# Rocket_Controller_ver2_00.net
KiCad netlist of a schematic drawn in EAGLE
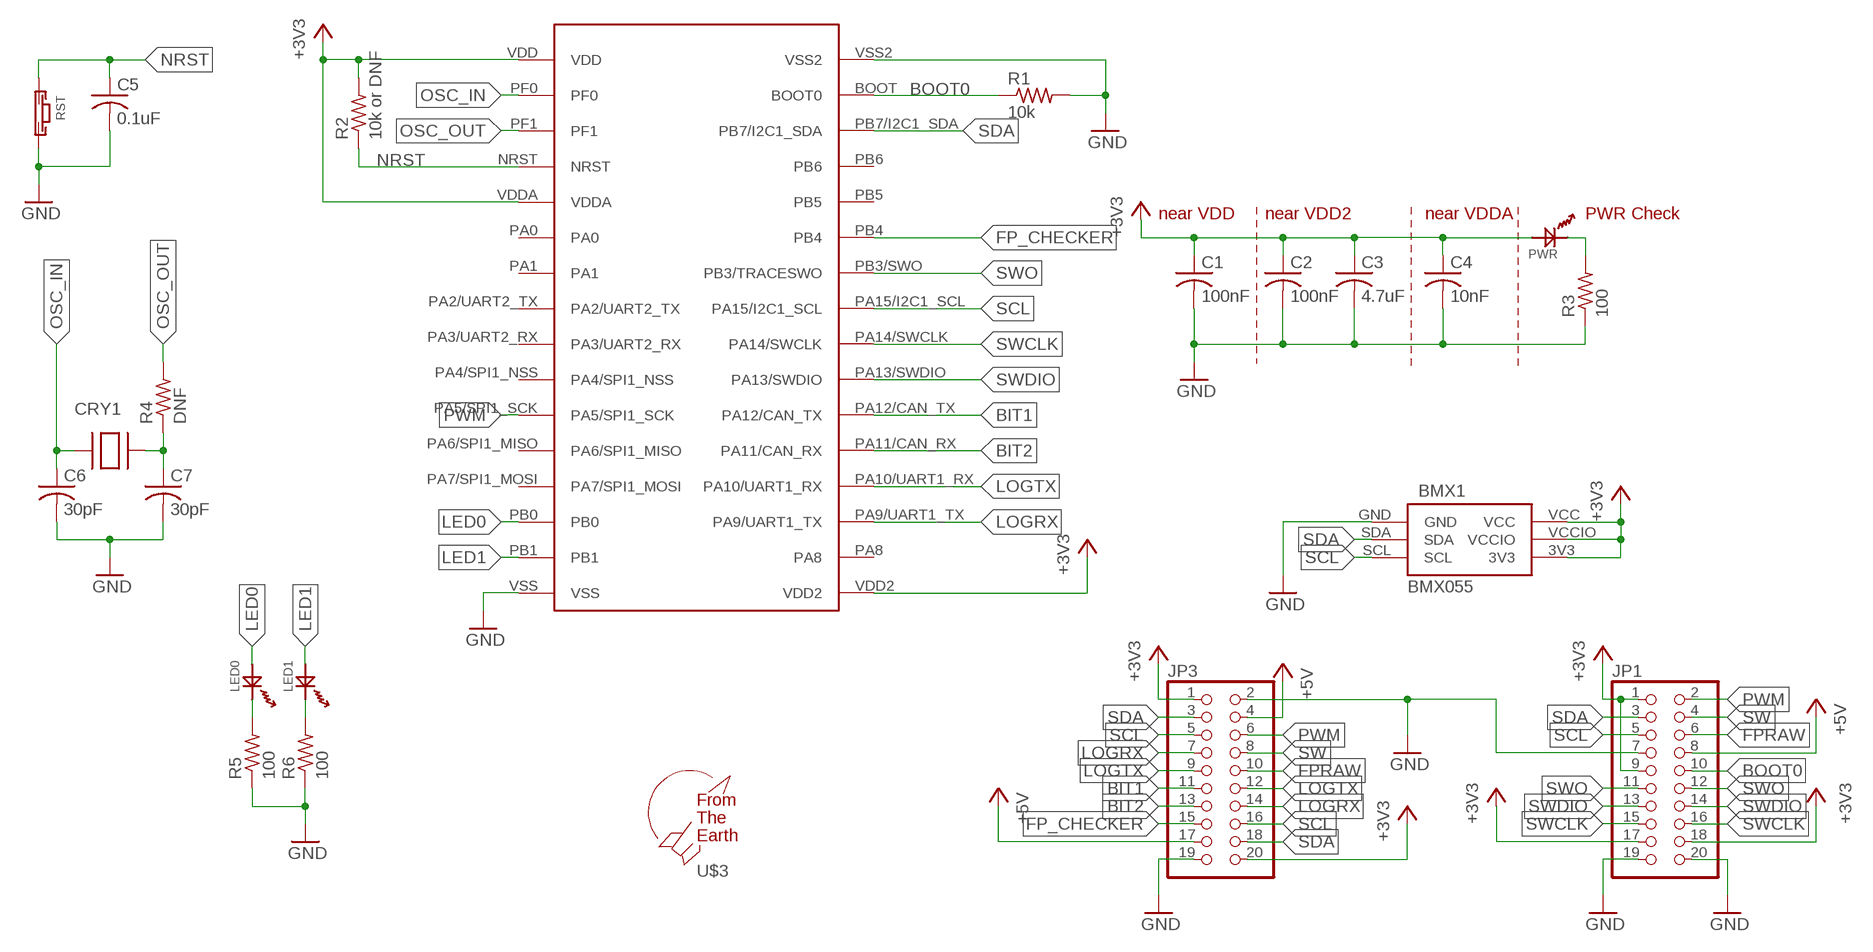
[diagram p0: schematic, sheet 1]

(export (version "E")
  (design (tool "Eeschema 10.0.6"))
  (components
    (comp (ref "BMX1")
      (value "BMX055")
      (footprint "eagle-import:BMX055")
      (libsource (lib "eagle-import") (part "BMX055"))
    )
    (comp (ref "C1")
      (value "100nF")
      (footprint "eagle-import:C1608")
      (libsource (lib "eagle-import") (part "C-USC1608"))
    )
    (comp (ref "C2")
      (value "100nF")
      (footprint "eagle-import:C1608")
      (libsource (lib "eagle-import") (part "C-USC1608"))
    )
    (comp (ref "C3")
      (value "4.7uF")
      (footprint "eagle-import:C1608")
      (libsource (lib "eagle-import") (part "C-USC1608"))
    )
    (comp (ref "C4")
      (value "10nF")
      (footprint "eagle-import:C1608")
      (libsource (lib "eagle-import") (part "C-USC1608"))
    )
    (comp (ref "C5")
      (value "0.1uF")
      (footprint "eagle-import:C1608")
      (libsource (lib "eagle-import") (part "C-USC1608"))
    )
    (comp (ref "C6")
      (value "30pF")
      (footprint "eagle-import:C1608")
      (libsource (lib "eagle-import") (part "C-USC1608"))
    )
    (comp (ref "C7")
      (value "30pF")
      (footprint "eagle-import:C1608")
      (libsource (lib "eagle-import") (part "C-USC1608"))
    )
    (comp (ref "CRY1")
      (value "8MHZ")
      (footprint "eagle-import:CRYSTAL")
      (libsource (lib "eagle-import") (part "8MHZ"))
    )
    (comp (ref "JP1")
      (value "PINHD-2X10/90")
      (footprint "eagle-import:2X10_90")
      (libsource (lib "eagle-import") (part "PINHD-2X10/90"))
    )
    (comp (ref "JP3")
      (value "PINHD-2X10/90")
      (footprint "eagle-import:2X10_90")
      (libsource (lib "eagle-import") (part "PINHD-2X10/90"))
    )
    (comp (ref "LED0")
      (value "OSXX1608C1A")
      (footprint "eagle-import:OSXX1608C1A")
      (libsource (lib "eagle-import") (part "OSXX1608C1A"))
    )
    (comp (ref "LED1")
      (value "OSXX1608C1A")
      (footprint "eagle-import:OSXX1608C1A")
      (libsource (lib "eagle-import") (part "OSXX1608C1A"))
    )
    (comp (ref "PWR")
      (value "OSXX1608C1A")
      (footprint "eagle-import:OSXX1608C1A")
      (libsource (lib "eagle-import") (part "OSXX1608C1A"))
    )
    (comp (ref "R1")
      (value "10k")
      (footprint "eagle-import:R0603")
      (libsource (lib "eagle-import") (part "R-US_R0603"))
    )
    (comp (ref "R2")
      (value "10k or DNF")
      (footprint "eagle-import:R0603")
      (libsource (lib "eagle-import") (part "R-US_R0603"))
    )
    (comp (ref "R3")
      (value "100")
      (footprint "eagle-import:R0603")
      (libsource (lib "eagle-import") (part "R-US_R0603"))
    )
    (comp (ref "R4")
      (value "DNF")
      (footprint "eagle-import:R0603")
      (libsource (lib "eagle-import") (part "R-US_R0603"))
    )
    (comp (ref "R5")
      (value "100")
      (footprint "eagle-import:R0603")
      (libsource (lib "eagle-import") (part "R-US_R0603"))
    )
    (comp (ref "R6")
      (value "100")
      (footprint "eagle-import:R0603")
      (libsource (lib "eagle-import") (part "R-US_R0603"))
    )
    (comp (ref "RST")
      (value "TVAF06-A020B-R")
      (footprint "eagle-import:TVAF06-A020B-R")
      (libsource (lib "eagle-import") (part "TVAF06-A020B-R"))
    )
    (comp (ref "U$1")
      (value "STM32F303K8")
      (footprint "eagle-import:STM32F303K8")
      (libsource (lib "eagle-import") (part "STM32F303K8"))
    )
    (comp (ref "U$3")
      (value "F.T.E.LOGO")
      (footprint "eagle-import:LOGO")
      (libsource (lib "eagle-import") (part "F.T.E.LOGO"))
    )
  )
  (nets
    (net (code "1") (name "+3V3") (class "Default")
      (node (ref "BMX1") (pin "3V3") (pinfunction "3V3_3V3") (pintype "power_in"))
      (node (ref "BMX1") (pin "VCC") (pinfunction "VCC_VCC") (pintype "power_in"))
      (node (ref "BMX1") (pin "VCCIO") (pinfunction "VCCIO_VCCIO") (pintype "power_in"))
      (node (ref "C1") (pin "1") (pinfunction "1_1") (pintype "passive"))
      (node (ref "C2") (pin "1") (pinfunction "1_1") (pintype "passive"))
      (node (ref "C3") (pin "1") (pinfunction "1_1") (pintype "passive"))
      (node (ref "C4") (pin "1") (pinfunction "1_1") (pintype "passive"))
      (node (ref "JP1") (pin "1") (pinfunction "1_1") (pintype "passive"))
      (node (ref "JP1") (pin "17") (pinfunction "17_17") (pintype "passive"))
      (node (ref "JP1") (pin "18") (pinfunction "18_18") (pintype "passive"))
      (node (ref "JP1") (pin "9") (pinfunction "9_9") (pintype "passive"))
      (node (ref "JP3") (pin "1") (pinfunction "1_1") (pintype "passive"))
      (node (ref "JP3") (pin "20") (pinfunction "20_20") (pintype "passive"))
      (node (ref "PWR") (pin "AN") (pinfunction "AN_AN") (pintype "bidirectional"))
      (node (ref "R2") (pin "2") (pinfunction "2_2") (pintype "passive"))
      (node (ref "U$1") (pin "VDD") (pinfunction "VDD_VDD") (pintype "power_in"))
      (node (ref "U$1") (pin "VDD2") (pinfunction "VDD2_VDD2") (pintype "power_in"))
      (node (ref "U$1") (pin "VDDA") (pinfunction "VDDA_VDDA") (pintype "power_in"))
    )
    (net (code "2") (name "+5V") (class "Default")
      (node (ref "JP1") (pin "8") (pinfunction "8_8") (pintype "passive"))
      (node (ref "JP3") (pin "17") (pinfunction "17_17") (pintype "passive"))
      (node (ref "JP3") (pin "4") (pinfunction "4_4") (pintype "passive"))
    )
    (net (code "3") (name "BIT1") (class "Default")
      (node (ref "JP3") (pin "11") (pinfunction "11_11") (pintype "passive"))
      (node (ref "U$1") (pin "PA12/CAN_TX") (pinfunction "PA12/CAN_TX_PA12/CAN_TX") (pintype "bidirectional"))
    )
    (net (code "4") (name "BIT2") (class "Default")
      (node (ref "JP3") (pin "13") (pinfunction "13_13") (pintype "passive"))
      (node (ref "U$1") (pin "PA11/CAN_RX") (pinfunction "PA11/CAN_RX_PA11/CAN_RX") (pintype "bidirectional"))
    )
    (net (code "5") (name "BOOT0") (class "Default")
      (node (ref "JP1") (pin "10") (pinfunction "10_10") (pintype "passive"))
      (node (ref "R1") (pin "1") (pinfunction "1_1") (pintype "passive"))
      (node (ref "U$1") (pin "BOOT") (pinfunction "BOOT0_BOOT") (pintype "bidirectional"))
    )
    (net (code "6") (name "FPRAW") (class "Default")
      (node (ref "JP1") (pin "6") (pinfunction "6_6") (pintype "passive"))
      (node (ref "JP3") (pin "10") (pinfunction "10_10") (pintype "passive"))
    )
    (net (code "7") (name "FP_CHECKER") (class "Default")
      (node (ref "JP3") (pin "15") (pinfunction "15_15") (pintype "passive"))
      (node (ref "U$1") (pin "PB4") (pinfunction "PB4_PB4") (pintype "bidirectional"))
    )
    (net (code "8") (name "GND") (class "Default")
      (node (ref "BMX1") (pin "GND") (pinfunction "GND_GND") (pintype "power_in"))
      (node (ref "C1") (pin "2") (pinfunction "2_2") (pintype "passive"))
      (node (ref "C2") (pin "2") (pinfunction "2_2") (pintype "passive"))
      (node (ref "C3") (pin "2") (pinfunction "2_2") (pintype "passive"))
      (node (ref "C4") (pin "2") (pinfunction "2_2") (pintype "passive"))
      (node (ref "C5") (pin "2") (pinfunction "2_2") (pintype "passive"))
      (node (ref "C6") (pin "2") (pinfunction "2_2") (pintype "passive"))
      (node (ref "C7") (pin "2") (pinfunction "2_2") (pintype "passive"))
      (node (ref "JP1") (pin "19") (pinfunction "19_19") (pintype "passive"))
      (node (ref "JP1") (pin "20") (pinfunction "20_20") (pintype "passive"))
      (node (ref "JP1") (pin "7") (pinfunction "7_7") (pintype "passive"))
      (node (ref "JP3") (pin "19") (pinfunction "19_19") (pintype "passive"))
      (node (ref "JP3") (pin "2") (pinfunction "2_2") (pintype "passive"))
      (node (ref "R1") (pin "2") (pinfunction "2_2") (pintype "passive"))
      (node (ref "R3") (pin "1") (pinfunction "1_1") (pintype "passive"))
      (node (ref "R5") (pin "1") (pinfunction "1_1") (pintype "passive"))
      (node (ref "R6") (pin "1") (pinfunction "1_1") (pintype "passive"))
      (node (ref "RST") (pin "P$2") (pinfunction "P$2_P$2") (pintype "bidirectional"))
      (node (ref "U$1") (pin "VSS") (pinfunction "VSS_VSS") (pintype "power_in"))
      (node (ref "U$1") (pin "VSS2") (pinfunction "VSS2_VSS2") (pintype "power_in"))
    )
    (net (code "9") (name "LED0") (class "Default")
      (node (ref "LED0") (pin "AN") (pinfunction "AN_AN") (pintype "bidirectional"))
      (node (ref "U$1") (pin "PB0") (pinfunction "PB0_PB0") (pintype "bidirectional"))
    )
    (net (code "10") (name "LED1") (class "Default")
      (node (ref "LED1") (pin "AN") (pinfunction "AN_AN") (pintype "bidirectional"))
      (node (ref "U$1") (pin "PB1") (pinfunction "PB1_PB1") (pintype "bidirectional"))
    )
    (net (code "11") (name "LOGRX") (class "Default")
      (node (ref "JP3") (pin "14") (pinfunction "14_14") (pintype "passive"))
      (node (ref "JP3") (pin "7") (pinfunction "7_7") (pintype "passive"))
      (node (ref "U$1") (pin "PA9/UART1_TX") (pinfunction "PA9/UART1_TX_PA9/UART1_TX") (pintype "bidirectional"))
    )
    (net (code "12") (name "LOGTX") (class "Default")
      (node (ref "JP3") (pin "12") (pinfunction "12_12") (pintype "passive"))
      (node (ref "JP3") (pin "9") (pinfunction "9_9") (pintype "passive"))
      (node (ref "U$1") (pin "PA10/UART1_RX") (pinfunction "PA10/UART1_RX_PA10/UART1_RX") (pintype "bidirectional"))
    )
    (net (code "13") (name "NRST") (class "Default")
      (node (ref "C5") (pin "1") (pinfunction "1_1") (pintype "passive"))
      (node (ref "R2") (pin "1") (pinfunction "1_1") (pintype "passive"))
      (node (ref "RST") (pin "P$1") (pinfunction "P$1_P$1") (pintype "bidirectional"))
      (node (ref "U$1") (pin "NRST") (pinfunction "NRST_NRST") (pintype "bidirectional"))
    )
    (net (code "14") (name "Net-(C7-Pad1)") (class "Default")
      (node (ref "C7") (pin "1") (pinfunction "1_1") (pintype "passive"))
      (node (ref "CRY1") (pin "P$2") (pinfunction "P$2_P$2") (pintype "bidirectional"))
      (node (ref "R4") (pin "1") (pinfunction "1_1") (pintype "passive"))
    )
    (net (code "15") (name "Net-(LED0-PadCT)") (class "Default")
      (node (ref "LED0") (pin "CT") (pinfunction "CT_CT") (pintype "bidirectional"))
      (node (ref "R5") (pin "2") (pinfunction "2_2") (pintype "passive"))
    )
    (net (code "16") (name "Net-(LED1-PadCT)") (class "Default")
      (node (ref "LED1") (pin "CT") (pinfunction "CT_CT") (pintype "bidirectional"))
      (node (ref "R6") (pin "2") (pinfunction "2_2") (pintype "passive"))
    )
    (net (code "17") (name "Net-(PWR-PadCT)") (class "Default")
      (node (ref "PWR") (pin "CT") (pinfunction "CT_CT") (pintype "bidirectional"))
      (node (ref "R3") (pin "2") (pinfunction "2_2") (pintype "passive"))
    )
    (net (code "18") (name "OSC_IN") (class "Default")
      (node (ref "C6") (pin "1") (pinfunction "1_1") (pintype "passive"))
      (node (ref "CRY1") (pin "P$1") (pinfunction "P$1_P$1") (pintype "bidirectional"))
      (node (ref "U$1") (pin "PF0") (pinfunction "PF0_PF0") (pintype "bidirectional"))
    )
    (net (code "19") (name "OSC_OUT") (class "Default")
      (node (ref "R4") (pin "2") (pinfunction "2_2") (pintype "passive"))
      (node (ref "U$1") (pin "PF1") (pinfunction "PF1_PF1") (pintype "bidirectional"))
    )
    (net (code "20") (name "PWM") (class "Default")
      (node (ref "JP1") (pin "2") (pinfunction "2_2") (pintype "passive"))
      (node (ref "JP3") (pin "6") (pinfunction "6_6") (pintype "passive"))
      (node (ref "U$1") (pin "PA5/SPI1_SCK") (pinfunction "PA5/SPI1_SCK_PA5/SPI1_SCK") (pintype "bidirectional"))
    )
    (net (code "21") (name "SCL") (class "Default")
      (node (ref "BMX1") (pin "SCL") (pinfunction "SCL_SCL") (pintype "bidirectional"))
      (node (ref "JP1") (pin "5") (pinfunction "5_5") (pintype "passive"))
      (node (ref "JP3") (pin "16") (pinfunction "16_16") (pintype "passive"))
      (node (ref "JP3") (pin "5") (pinfunction "5_5") (pintype "passive"))
      (node (ref "U$1") (pin "PA15/I2C1_SCL") (pinfunction "PA15/I2C1_SCL_PA15/I2C1_SCL") (pintype "bidirectional"))
    )
    (net (code "22") (name "SDA") (class "Default")
      (node (ref "BMX1") (pin "SDA") (pinfunction "SDA_SDA") (pintype "bidirectional"))
      (node (ref "JP1") (pin "3") (pinfunction "3_3") (pintype "passive"))
      (node (ref "JP3") (pin "18") (pinfunction "18_18") (pintype "passive"))
      (node (ref "JP3") (pin "3") (pinfunction "3_3") (pintype "passive"))
      (node (ref "U$1") (pin "PB7/I2C1_SDA") (pinfunction "PB7/I2C1_SDA_PB7/I2C1_SDA") (pintype "bidirectional"))
    )
    (net (code "23") (name "SW") (class "Default")
      (node (ref "JP1") (pin "4") (pinfunction "4_4") (pintype "passive"))
      (node (ref "JP3") (pin "8") (pinfunction "8_8") (pintype "passive"))
    )
    (net (code "24") (name "SWCLK") (class "Default")
      (node (ref "JP1") (pin "15") (pinfunction "15_15") (pintype "passive"))
      (node (ref "JP1") (pin "16") (pinfunction "16_16") (pintype "passive"))
      (node (ref "U$1") (pin "PA14/SWCLK") (pinfunction "PA14/SWCLK_PA14/SWCLK") (pintype "bidirectional"))
    )
    (net (code "25") (name "SWDIO") (class "Default")
      (node (ref "JP1") (pin "13") (pinfunction "13_13") (pintype "passive"))
      (node (ref "JP1") (pin "14") (pinfunction "14_14") (pintype "passive"))
      (node (ref "U$1") (pin "PA13/SWDIO") (pinfunction "PA13/SWDIO_PA13/SWDIO") (pintype "bidirectional"))
    )
    (net (code "26") (name "SWO") (class "Default")
      (node (ref "JP1") (pin "11") (pinfunction "11_11") (pintype "passive"))
      (node (ref "JP1") (pin "12") (pinfunction "12_12") (pintype "passive"))
      (node (ref "U$1") (pin "PB3/SWO") (pinfunction "PB3/TRACESWO_PB3/SWO") (pintype "bidirectional"))
    )
    (net (code "27") (name "unconnected-(U$1-PadPA0)") (class "Default")
      (node (ref "U$1") (pin "PA0") (pinfunction "PA0_PA0") (pintype "bidirectional"))
    )
    (net (code "28") (name "unconnected-(U$1-PadPA1)") (class "Default")
      (node (ref "U$1") (pin "PA1") (pinfunction "PA1_PA1") (pintype "bidirectional"))
    )
    (net (code "29") (name "unconnected-(U$1-PadPA2{slash}UART2_TX)") (class "Default")
      (node (ref "U$1") (pin "PA2/UART2_TX") (pinfunction "PA2/UART2_TX_PA2/UART2_TX") (pintype "bidirectional"))
    )
    (net (code "30") (name "unconnected-(U$1-PadPA3{slash}UART2_RX)") (class "Default")
      (node (ref "U$1") (pin "PA3/UART2_RX") (pinfunction "PA3/UART2_RX_PA3/UART2_RX") (pintype "bidirectional"))
    )
    (net (code "31") (name "unconnected-(U$1-PadPA4{slash}SPI1_NSS)") (class "Default")
      (node (ref "U$1") (pin "PA4/SPI1_NSS") (pinfunction "PA4/SPI1_NSS_PA4/SPI1_NSS") (pintype "bidirectional"))
    )
    (net (code "32") (name "unconnected-(U$1-PadPA6{slash}SPI1_MISO)") (class "Default")
      (node (ref "U$1") (pin "PA6/SPI1_MISO") (pinfunction "PA6/SPI1_MISO_PA6/SPI1_MISO") (pintype "bidirectional"))
    )
    (net (code "33") (name "unconnected-(U$1-PadPA7{slash}SPI1_MOSI)") (class "Default")
      (node (ref "U$1") (pin "PA7/SPI1_MOSI") (pinfunction "PA7/SPI1_MOSI_PA7/SPI1_MOSI") (pintype "bidirectional"))
    )
    (net (code "34") (name "unconnected-(U$1-PadPA8)") (class "Default")
      (node (ref "U$1") (pin "PA8") (pinfunction "PA8_PA8") (pintype "bidirectional"))
    )
    (net (code "35") (name "unconnected-(U$1-PadPB5)") (class "Default")
      (node (ref "U$1") (pin "PB5") (pinfunction "PB5_PB5") (pintype "bidirectional"))
    )
    (net (code "36") (name "unconnected-(U$1-PadPB6)") (class "Default")
      (node (ref "U$1") (pin "PB6") (pinfunction "PB6_PB6") (pintype "bidirectional"))
    )
  )
)
